# GroundStation.net
KiCad netlist of a schematic drawn in Altium Designer
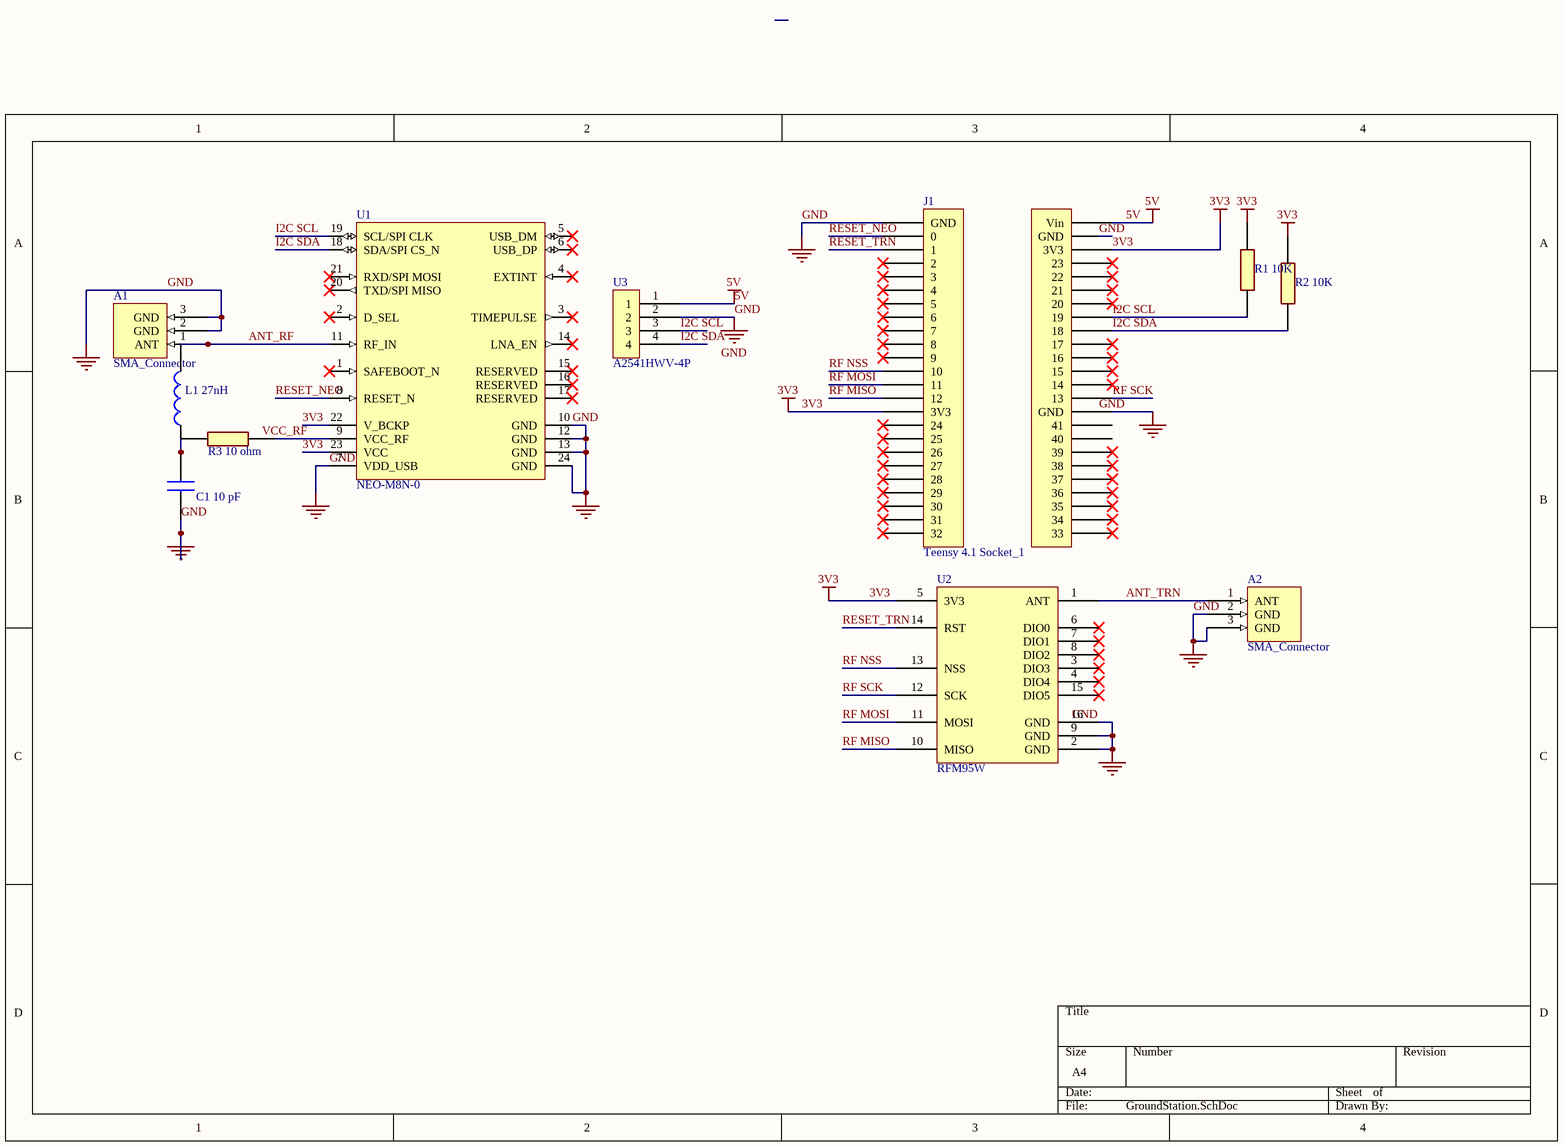
[diagram p0: GroundStation.SchDoc]

(export (version "E")
  (design (tool "Eeschema 10.0.6"))
  (components
    (comp (ref "A1")
      (value "SMA_Connector")
      (footprint "SMA Connector")
      (description "SMA Connector Side Board Connection Female Socket 50 ohms")
      (libsource (lib "") (part "SMA Connector_1"))
    )
    (comp (ref "A2")
      (value "SMA_Connector")
      (footprint "SMA Connector")
      (description "SMA Connector Side Board Connection Female Socket 50 ohms")
      (libsource (lib "Edward Spanner") (part "SMA Connector"))
    )
    (comp (ref "C1 10 pF")
      (value "CL21B103KBANNNC")
      (footprint "CAPC2012X75N")
      (fields (field (name "MOUSER PART NUMBER") "187-CL21B103KBANNNC"))
      (libsource (lib "Edward Spanner") (part "CL21B103KBANNNC"))
    )
    (comp (ref "J1")
      (value "Teensy 4.1 Socket_1")
      (footprint "Teensy 4.1 Socket")
      (description "2x 24POS, 2.54mm pitch header pins for socketing a Teensy 4.1")
      (libsource (lib "Edward Spanner") (part "Teensy 4.1 Socket_1"))
    )
    (comp (ref "L1 27nH")
      (value "LQG15HS27NJ02D")
      (footprint "LQG15WH0N7B02D")
      (fields (field (name "MOUSER PART NUMBER") "81-LQG15HS27NJ02D"))
      (libsource (lib "Edward Spanner") (part "LQG15HS27NJ02D"))
    )
    (comp (ref "R1 10K")
      (value "0402WGF1002TCE")
      (footprint "RESC1005X40N")
      (description "Chip Resistor - Surface Mount 10KOhms +/-1% 1/16W 0402 RoHS")
      (libsource (lib "Edward Spanner") (part "0402WGF1002TCE"))
    )
    (comp (ref "R2 10K")
      (value "0402WGF1002TCE")
      (footprint "RESC1005X40N")
      (description "Chip Resistor - Surface Mount 10KOhms +/-1% 1/16W 0402 RoHS")
      (libsource (lib "Edward Spanner") (part "0402WGF1002TCE"))
    )
    (comp (ref "R3 10 ohm")
      (value "0402WGF100JTCE")
      (footprint "RESC1005X40N")
      (description "Chip Resistor - Surface Mount 10Ohms +/-1% 1/16W 0402 RoHS")
      (libsource (lib "Edward Spanner") (part "0402WGF100JTCE"))
    )
    (comp (ref "U1")
      (value "NEO-M8N-0")
      (footprint "UBX-NEO-M8-24_V")
      (description "U-Blox M8 Concurrent Gnss Module, 3.6 V, -40 to 85 degC, 24-Pin SMD, RoHS, Tape and Reel")
      (fields (field (name "MANUFACTURER") "U-Blox"))
      (libsource (lib "Altium Content Vault") (part "UBX-NEO-M8X-24"))
    )
    (comp (ref "U2")
      (value "RFM95W")
      (footprint "RFM95CW")
      (description "LoRa Transceiver module 137-1020 MHz")
      (libsource (lib "Edward Spanner") (part "RFM95W"))
    )
    (comp (ref "U3")
      (value "A2541HWV-4P")
      (footprint "A2541HWV-4P")
      (description "1x4Pin connector throughhole, square holes")
      (libsource (lib "Edward Spanner") (part "A2541HWV-4P"))
    )
  )
  (nets
    (net (code "1") (name "/ANT_RF") (class "Default")
      (node (ref "A1") (pin "1") (pinfunction "ANT_1") (pintype "input"))
      (node (ref "L1 27nH") (pin "2") (pinfunction "2_2") (pintype "passive"))
      (node (ref "U1") (pin "11") (pinfunction "RF_IN_11") (pintype "input"))
    )
    (net (code "2") (name "/ANT_TRN") (class "Default")
      (node (ref "A2") (pin "1") (pinfunction "ANT_1") (pintype "input"))
      (node (ref "U2") (pin "1") (pinfunction "ANT_1") (pintype "passive"))
    )
    (net (code "3") (name "/I2C SCL") (class "Default")
      (node (ref "J1") (pin "17") (pinfunction "19_17") (pintype "passive"))
      (node (ref "R1 10K") (pin "1") (pinfunction "1_1") (pintype "passive"))
      (node (ref "U1") (pin "19") (pinfunction "SCL/SPI_CLK_19") (pintype "bidirectional"))
      (node (ref "U3") (pin "3") (pinfunction "3_3") (pintype "passive"))
    )
    (net (code "4") (name "/I2C SDA") (class "Default")
      (node (ref "J1") (pin "16") (pinfunction "18_16") (pintype "passive"))
      (node (ref "R2 10K") (pin "1") (pinfunction "1_1") (pintype "passive"))
      (node (ref "U1") (pin "18") (pinfunction "SDA/SPI_CS_N_18") (pintype "bidirectional"))
      (node (ref "U3") (pin "4") (pinfunction "4_4") (pintype "passive"))
    )
    (net (code "5") (name "/RESET_NEO") (class "Default")
      (node (ref "J1") (pin "47") (pinfunction "0_47") (pintype "passive"))
      (node (ref "U1") (pin "8") (pinfunction "RESET_N_8") (pintype "input"))
    )
    (net (code "6") (name "/RESET_TRN") (class "Default")
      (node (ref "J1") (pin "46") (pinfunction "1_46") (pintype "passive"))
      (node (ref "U2") (pin "14") (pinfunction "RST_14") (pintype "passive"))
    )
    (net (code "7") (name "/RF MISO") (class "Default")
      (node (ref "J1") (pin "35") (pinfunction "12_35") (pintype "passive"))
      (node (ref "U2") (pin "10") (pinfunction "MISO_10") (pintype "passive"))
    )
    (net (code "8") (name "/RF MOSI") (class "Default")
      (node (ref "J1") (pin "36") (pinfunction "11_36") (pintype "passive"))
      (node (ref "U2") (pin "11") (pinfunction "MOSI_11") (pintype "passive"))
    )
    (net (code "9") (name "/RF NSS") (class "Default")
      (node (ref "J1") (pin "37") (pinfunction "10_37") (pintype "passive"))
      (node (ref "U2") (pin "13") (pinfunction "NSS_13") (pintype "passive"))
    )
    (net (code "10") (name "/RF SCK") (class "Default")
      (node (ref "J1") (pin "11") (pinfunction "13_11") (pintype "passive"))
      (node (ref "U2") (pin "12") (pinfunction "SCK_12") (pintype "passive"))
    )
    (net (code "12") (name "3V3") (class "Default")
      (node (ref "J1") (pin "22") (pinfunction "3V3_22") (pintype "passive"))
      (node (ref "J1") (pin "34") (pinfunction "3V3_34") (pintype "passive"))
      (node (ref "R1 10K") (pin "2") (pinfunction "2_2") (pintype "passive"))
      (node (ref "R2 10K") (pin "2") (pinfunction "2_2") (pintype "passive"))
      (node (ref "U1") (pin "22") (pinfunction "V_BCKP_22") (pintype "power_in"))
      (node (ref "U1") (pin "23") (pinfunction "VCC_23") (pintype "power_in"))
      (node (ref "U2") (pin "5") (pinfunction "3V3_5") (pintype "passive"))
    )
    (net (code "13") (name "5V") (class "Default")
      (node (ref "J1") (pin "24") (pinfunction "Vin_24") (pintype "passive"))
      (node (ref "U3") (pin "1") (pinfunction "1_1") (pintype "passive"))
    )
    (net (code "14") (name "GND") (class "Default")
      (node (ref "A1") (pin "2") (pinfunction "GND_2") (pintype "input"))
      (node (ref "A1") (pin "3") (pinfunction "GND_3") (pintype "input"))
      (node (ref "A2") (pin "2") (pinfunction "GND_2") (pintype "input"))
      (node (ref "A2") (pin "3") (pinfunction "GND_3") (pintype "input"))
      (node (ref "C1 10 pF") (pin "1") (pinfunction "1_1") (pintype "passive"))
      (node (ref "J1") (pin "10") (pinfunction "GND_10") (pintype "passive"))
      (node (ref "J1") (pin "23") (pinfunction "GND_23") (pintype "passive"))
      (node (ref "J1") (pin "48") (pinfunction "GND_48") (pintype "passive"))
      (node (ref "U1") (pin "10") (pinfunction "GND_10") (pintype "power_in"))
      (node (ref "U1") (pin "12") (pinfunction "GND_12") (pintype "power_in"))
      (node (ref "U1") (pin "13") (pinfunction "GND_13") (pintype "power_in"))
      (node (ref "U1") (pin "24") (pinfunction "GND_24") (pintype "power_in"))
      (node (ref "U1") (pin "7") (pinfunction "VDD_USB_7") (pintype "power_in"))
      (node (ref "U2") (pin "16") (pinfunction "GND_16") (pintype "passive"))
      (node (ref "U2") (pin "2") (pinfunction "GND_2") (pintype "passive"))
      (node (ref "U2") (pin "9") (pinfunction "GND_9") (pintype "passive"))
      (node (ref "U3") (pin "2") (pinfunction "2_2") (pintype "passive"))
    )
    (net (code "15") (name "Net-(C1 10 pF-Pad2)") (class "Default")
      (node (ref "C1 10 pF") (pin "2") (pinfunction "2_2") (pintype "passive"))
      (node (ref "L1 27nH") (pin "1") (pinfunction "1_1") (pintype "passive"))
      (node (ref "R3 10 ohm") (pin "1") (pinfunction "1_1") (pintype "passive"))
    )
    (net (code "16") (name "Net-(U1-VCC_RF)") (class "Default")
      (node (ref "R3 10 ohm") (pin "2") (pinfunction "2_2") (pintype "passive"))
      (node (ref "U1") (pin "9") (pinfunction "VCC_RF_9") (pintype "power_in"))
    )
    (net (code "17") (name "unconnected-(J1-2-Pad45)") (class "Default")
      (node (ref "J1") (pin "45") (pinfunction "2_45") (pintype "passive+no_connect"))
    )
    (net (code "18") (name "unconnected-(J1-3-Pad44)") (class "Default")
      (node (ref "J1") (pin "44") (pinfunction "3_44") (pintype "passive+no_connect"))
    )
    (net (code "19") (name "unconnected-(J1-4-Pad43)") (class "Default")
      (node (ref "J1") (pin "43") (pinfunction "4_43") (pintype "passive+no_connect"))
    )
    (net (code "20") (name "unconnected-(J1-5-Pad42)") (class "Default")
      (node (ref "J1") (pin "42") (pinfunction "5_42") (pintype "passive+no_connect"))
    )
    (net (code "21") (name "unconnected-(J1-6-Pad41)") (class "Default")
      (node (ref "J1") (pin "41") (pinfunction "6_41") (pintype "passive+no_connect"))
    )
    (net (code "22") (name "unconnected-(J1-7-Pad40)") (class "Default")
      (node (ref "J1") (pin "40") (pinfunction "7_40") (pintype "passive+no_connect"))
    )
    (net (code "23") (name "unconnected-(J1-8-Pad39)") (class "Default")
      (node (ref "J1") (pin "39") (pinfunction "8_39") (pintype "passive+no_connect"))
    )
    (net (code "24") (name "unconnected-(J1-9-Pad38)") (class "Default")
      (node (ref "J1") (pin "38") (pinfunction "9_38") (pintype "passive+no_connect"))
    )
    (net (code "25") (name "unconnected-(J1-14-Pad12)") (class "Default")
      (node (ref "J1") (pin "12") (pinfunction "14_12") (pintype "passive+no_connect"))
    )
    (net (code "26") (name "unconnected-(J1-15-Pad13)") (class "Default")
      (node (ref "J1") (pin "13") (pinfunction "15_13") (pintype "passive+no_connect"))
    )
    (net (code "27") (name "unconnected-(J1-16-Pad14)") (class "Default")
      (node (ref "J1") (pin "14") (pinfunction "16_14") (pintype "passive+no_connect"))
    )
    (net (code "28") (name "unconnected-(J1-17-Pad15)") (class "Default")
      (node (ref "J1") (pin "15") (pinfunction "17_15") (pintype "passive+no_connect"))
    )
    (net (code "29") (name "unconnected-(J1-20-Pad18)") (class "Default")
      (node (ref "J1") (pin "18") (pinfunction "20_18") (pintype "passive+no_connect"))
    )
    (net (code "30") (name "unconnected-(J1-21-Pad19)") (class "Default")
      (node (ref "J1") (pin "19") (pinfunction "21_19") (pintype "passive+no_connect"))
    )
    (net (code "31") (name "unconnected-(J1-22-Pad20)") (class "Default")
      (node (ref "J1") (pin "20") (pinfunction "22_20") (pintype "passive+no_connect"))
    )
    (net (code "32") (name "unconnected-(J1-23-Pad21)") (class "Default")
      (node (ref "J1") (pin "21") (pinfunction "23_21") (pintype "passive+no_connect"))
    )
    (net (code "33") (name "unconnected-(J1-24-Pad33)") (class "Default")
      (node (ref "J1") (pin "33") (pinfunction "24_33") (pintype "passive+no_connect"))
    )
    (net (code "34") (name "unconnected-(J1-25-Pad32)") (class "Default")
      (node (ref "J1") (pin "32") (pinfunction "25_32") (pintype "passive+no_connect"))
    )
    (net (code "35") (name "unconnected-(J1-26-Pad31)") (class "Default")
      (node (ref "J1") (pin "31") (pinfunction "26_31") (pintype "passive+no_connect"))
    )
    (net (code "36") (name "unconnected-(J1-27-Pad30)") (class "Default")
      (node (ref "J1") (pin "30") (pinfunction "27_30") (pintype "passive+no_connect"))
    )
    (net (code "37") (name "unconnected-(J1-28-Pad29)") (class "Default")
      (node (ref "J1") (pin "29") (pinfunction "28_29") (pintype "passive+no_connect"))
    )
    (net (code "38") (name "unconnected-(J1-29-Pad28)") (class "Default")
      (node (ref "J1") (pin "28") (pinfunction "29_28") (pintype "passive+no_connect"))
    )
    (net (code "39") (name "unconnected-(J1-30-Pad27)") (class "Default")
      (node (ref "J1") (pin "27") (pinfunction "30_27") (pintype "passive+no_connect"))
    )
    (net (code "40") (name "unconnected-(J1-31-Pad26)") (class "Default")
      (node (ref "J1") (pin "26") (pinfunction "31_26") (pintype "passive+no_connect"))
    )
    (net (code "41") (name "unconnected-(J1-32-Pad25)") (class "Default")
      (node (ref "J1") (pin "25") (pinfunction "32_25") (pintype "passive+no_connect"))
    )
    (net (code "42") (name "unconnected-(J1-33-Pad1)") (class "Default")
      (node (ref "J1") (pin "1") (pinfunction "33_1") (pintype "passive+no_connect"))
    )
    (net (code "43") (name "unconnected-(J1-34-Pad2)") (class "Default")
      (node (ref "J1") (pin "2") (pinfunction "34_2") (pintype "passive+no_connect"))
    )
    (net (code "44") (name "unconnected-(J1-35-Pad3)") (class "Default")
      (node (ref "J1") (pin "3") (pinfunction "35_3") (pintype "passive+no_connect"))
    )
    (net (code "45") (name "unconnected-(J1-36-Pad4)") (class "Default")
      (node (ref "J1") (pin "4") (pinfunction "36_4") (pintype "passive+no_connect"))
    )
    (net (code "46") (name "unconnected-(J1-37-Pad5)") (class "Default")
      (node (ref "J1") (pin "5") (pinfunction "37_5") (pintype "passive+no_connect"))
    )
    (net (code "47") (name "unconnected-(J1-38-Pad6)") (class "Default")
      (node (ref "J1") (pin "6") (pinfunction "38_6") (pintype "passive+no_connect"))
    )
    (net (code "48") (name "unconnected-(J1-39-Pad7)") (class "Default")
      (node (ref "J1") (pin "7") (pinfunction "39_7") (pintype "passive+no_connect"))
    )
    (net (code "49") (name "unconnected-(J1-40-Pad8)") (class "Default")
      (node (ref "J1") (pin "8") (pinfunction "40_8") (pintype "passive"))
    )
    (net (code "50") (name "unconnected-(J1-41-Pad9)") (class "Default")
      (node (ref "J1") (pin "9") (pinfunction "41_9") (pintype "passive"))
    )
    (net (code "51") (name "unconnected-(U1-D_SEL-Pad2)") (class "Default")
      (node (ref "U1") (pin "2") (pinfunction "D_SEL_2") (pintype "input+no_connect"))
    )
    (net (code "52") (name "unconnected-(U1-EXTINT-Pad4)") (class "Default")
      (node (ref "U1") (pin "4") (pinfunction "EXTINT_4") (pintype "input+no_connect"))
    )
    (net (code "53") (name "unconnected-(U1-LNA_EN-Pad14)") (class "Default")
      (node (ref "U1") (pin "14") (pinfunction "LNA_EN_14") (pintype "output+no_connect"))
    )
    (net (code "54") (name "unconnected-(U1-RESERVED-Pad15)") (class "Default")
      (node (ref "U1") (pin "15") (pinfunction "RESERVED_15") (pintype "passive+no_connect"))
    )
    (net (code "55") (name "unconnected-(U1-RESERVED-Pad16)") (class "Default")
      (node (ref "U1") (pin "16") (pinfunction "RESERVED_16") (pintype "passive+no_connect"))
    )
    (net (code "56") (name "unconnected-(U1-RESERVED-Pad17)") (class "Default")
      (node (ref "U1") (pin "17") (pinfunction "RESERVED_17") (pintype "passive+no_connect"))
    )
    (net (code "57") (name "unconnected-(U1-RXD{slash}SPI_MOSI-Pad21)") (class "Default")
      (node (ref "U1") (pin "21") (pinfunction "RXD/SPI_MOSI_21") (pintype "input+no_connect"))
    )
    (net (code "58") (name "unconnected-(U1-SAFEBOOT_N-Pad1)") (class "Default")
      (node (ref "U1") (pin "1") (pinfunction "SAFEBOOT_N_1") (pintype "input+no_connect"))
    )
    (net (code "59") (name "unconnected-(U1-TIMEPULSE-Pad3)") (class "Default")
      (node (ref "U1") (pin "3") (pinfunction "TIMEPULSE_3") (pintype "output+no_connect"))
    )
    (net (code "60") (name "unconnected-(U1-TXD{slash}SPI_MISO-Pad20)") (class "Default")
      (node (ref "U1") (pin "20") (pinfunction "TXD/SPI_MISO_20") (pintype "output+no_connect"))
    )
    (net (code "61") (name "unconnected-(U1-USB_DM-Pad5)") (class "Default")
      (node (ref "U1") (pin "5") (pinfunction "USB_DM_5") (pintype "bidirectional+no_connect"))
    )
    (net (code "62") (name "unconnected-(U1-USB_DP-Pad6)") (class "Default")
      (node (ref "U1") (pin "6") (pinfunction "USB_DP_6") (pintype "bidirectional+no_connect"))
    )
    (net (code "63") (name "unconnected-(U2-DIO0-Pad6)") (class "Default")
      (node (ref "U2") (pin "6") (pinfunction "DIO0_6") (pintype "passive+no_connect"))
    )
    (net (code "64") (name "unconnected-(U2-DIO1-Pad7)") (class "Default")
      (node (ref "U2") (pin "7") (pinfunction "DIO1_7") (pintype "passive+no_connect"))
    )
    (net (code "65") (name "unconnected-(U2-DIO2-Pad8)") (class "Default")
      (node (ref "U2") (pin "8") (pinfunction "DIO2_8") (pintype "passive+no_connect"))
    )
    (net (code "66") (name "unconnected-(U2-DIO3-Pad3)") (class "Default")
      (node (ref "U2") (pin "3") (pinfunction "DIO3_3") (pintype "passive+no_connect"))
    )
    (net (code "67") (name "unconnected-(U2-DIO4-Pad4)") (class "Default")
      (node (ref "U2") (pin "4") (pinfunction "DIO4_4") (pintype "passive+no_connect"))
    )
    (net (code "68") (name "unconnected-(U2-DIO5-Pad15)") (class "Default")
      (node (ref "U2") (pin "15") (pinfunction "DIO5_15") (pintype "passive+no_connect"))
    )
  )
)
